# Sheet1.net
KiCad netlist of a schematic drawn in Altium Designer
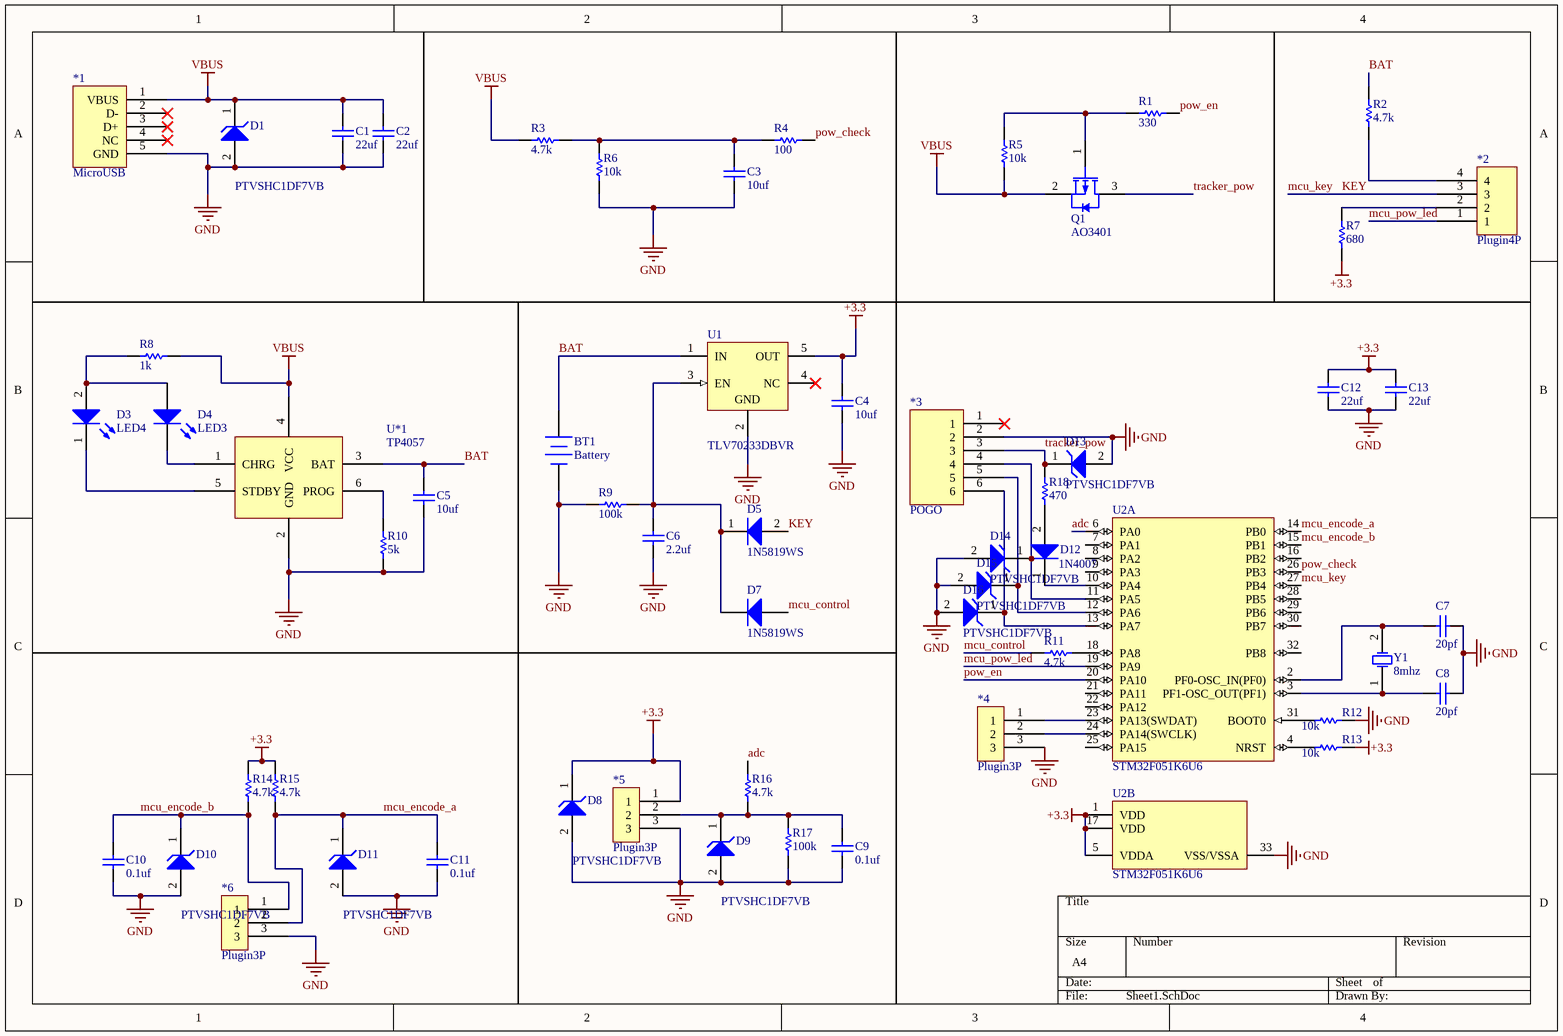
[diagram p0: Sheet1.SchDoc]

(export (version "E")
  (design (tool "Eeschema 10.0.6"))
  (components
    (comp (ref "*1") (value "MicroUSB") (footprint "MicroUSB") (libsource (lib "Schlib1") (part "MicroUSB")))
    (comp (ref "*2") (value "Plugin4P") (footprint "PLUGIN4P") (libsource (lib "Schlib1") (part "Plugin4P")))
    (comp (ref "*3") (value "POGO") (footprint "POGO") (libsource (lib "Schlib1") (part "POGO")))
    (comp (ref "*4") (value "Plugin3P") (footprint "Plugin3P") (libsource (lib "Schlib1") (part "Plugin3P")))
    (comp (ref "*5") (value "Plugin3P") (footprint "Plugin3P") (libsource (lib "Schlib1") (part "Plugin3P")))
    (comp (ref "*6") (value "Plugin3P") (footprint "Plugin3P") (libsource (lib "Schlib1") (part "Plugin3P")))
    (comp (ref "BT1")
      (value "Battery")
      (footprint "BAT-2")
      (description "Multicell Battery")
      (fields (field (name "PUBLISHER") "Altium Limited"))
      (libsource (lib "Miscellaneous Devices") (part "Battery"))
    )
    (comp (ref "C1")
      (value "22uf")
      (footprint "RESC2013X65X40LL15T20")
      (description "Capacitor")
      (fields (field (name "PUBLISHER") "Altium Limited"))
      (libsource (lib "Miscellaneous Devices") (part "Cap"))
    )
    (comp (ref "C2")
      (value "22uf")
      (footprint "RESC2013X65X40LL15T20")
      (description "Capacitor")
      (fields (field (name "PUBLISHER") "Altium Limited"))
      (libsource (lib "Miscellaneous Devices") (part "Cap"))
    )
    (comp (ref "C3")
      (value "10uf")
      (footprint "RESC2013X65X40LL15T20")
      (description "Capacitor")
      (fields (field (name "PUBLISHER") "Altium Limited"))
      (libsource (lib "Miscellaneous Devices") (part "Cap"))
    )
    (comp (ref "C4")
      (value "10uf")
      (footprint "RESC2013X65X40LL15T20")
      (description "Capacitor")
      (fields (field (name "PUBLISHER") "Altium Limited"))
      (libsource (lib "Miscellaneous Devices") (part "Cap"))
    )
    (comp (ref "C5")
      (value "10uf")
      (footprint "RESC2013X65X40LL15T20")
      (description "Capacitor")
      (fields (field (name "PUBLISHER") "Altium Limited"))
      (libsource (lib "Miscellaneous Devices") (part "Cap"))
    )
    (comp (ref "C6")
      (value "2.2uf")
      (footprint "RESC2013X65X40LL15T20")
      (description "Capacitor")
      (fields (field (name "PUBLISHER") "Altium Limited"))
      (libsource (lib "Miscellaneous Devices") (part "Cap"))
    )
    (comp (ref "C7")
      (value "20pf")
      (footprint "RESC2013X65X40LL15T20")
      (description "Capacitor")
      (fields (field (name "PUBLISHER") "Altium Limited"))
      (libsource (lib "Miscellaneous Devices") (part "Cap"))
    )
    (comp (ref "C8")
      (value "20pf")
      (footprint "RESC2013X65X40LL15T20")
      (description "Capacitor")
      (fields (field (name "PUBLISHER") "Altium Limited"))
      (libsource (lib "Miscellaneous Devices") (part "Cap"))
    )
    (comp (ref "C9")
      (value "0.1uf")
      (footprint "RESC2013X65X40LL15T20")
      (description "Capacitor")
      (fields (field (name "PUBLISHER") "Altium Limited"))
      (libsource (lib "Miscellaneous Devices") (part "Cap"))
    )
    (comp (ref "C10")
      (value "0.1uf")
      (footprint "RESC2013X65X40LL15T20")
      (description "Capacitor")
      (fields (field (name "PUBLISHER") "Altium Limited"))
      (libsource (lib "Miscellaneous Devices") (part "Cap"))
    )
    (comp (ref "C11")
      (value "0.1uf")
      (footprint "RESC2013X65X40LL15T20")
      (description "Capacitor")
      (fields (field (name "PUBLISHER") "Altium Limited"))
      (libsource (lib "Miscellaneous Devices") (part "Cap"))
    )
    (comp (ref "C12")
      (value "22uf")
      (footprint "RESC2013X65X40LL15T20")
      (description "Capacitor")
      (fields (field (name "PUBLISHER") "Altium Limited"))
      (libsource (lib "Miscellaneous Devices") (part "Cap"))
    )
    (comp (ref "C13")
      (value "22uf")
      (footprint "RESC2013X65X40LL15T20")
      (description "Capacitor")
      (fields (field (name "PUBLISHER") "Altium Limited"))
      (libsource (lib "Miscellaneous Devices") (part "Cap"))
    )
    (comp (ref "D1")
      (value "PTVSHC1DF7VB")
      (footprint "ONSC-SOD-123-2-425-04_V")
      (description "Zener Voltage Regulator, 500 mW, 2-Pin SOD-123, Pb-Free, Tape and Reel")
      (fields (field (name "MANUFACTURER") "On Semiconductor") (field (name "PARTNUMBER") "MMSZ39T1G"))
      (libsource (lib "ON Semi Zener Diodes") (part "MMSZ39T1G"))
    )
    (comp (ref "D3")
      (value "LED4")
      (footprint "RESC2013X65X40LL15T20")
      (description "Typical BLUE SiC LED")
      (fields (field (name "PUBLISHER") "Altium Limited"))
      (libsource (lib "") (part "LED3_1"))
    )
    (comp (ref "D4")
      (value "LED3")
      (footprint "RESC2013X65X40LL15T20")
      (description "Typical BLUE SiC LED")
      (fields (field (name "PUBLISHER") "Altium Limited"))
      (libsource (lib "Miscellaneous Devices") (part "LED3"))
    )
    (comp (ref "D5")
      (value "1N5819WS")
      (footprint "ONSC-SOD-323-2-477-02_V")
      (description "3 Amp General Purpose Rectifier")
      (fields (field (name "PUBLISHER") "Altium Limited"))
      (libsource (lib "Miscellaneous Devices") (part "Diode 1N5402"))
    )
    (comp (ref "D7")
      (value "1N5819WS")
      (footprint "ONSC-SOD-323-2-477-02_V")
      (description "3 Amp General Purpose Rectifier")
      (fields (field (name "PUBLISHER") "Altium Limited"))
      (libsource (lib "") (part "Diode 1N5402_1"))
    )
    (comp (ref "D8")
      (value "PTVSHC1DF7VB")
      (footprint "ONSC-SOD-123-2-425-04_V")
      (description "Zener Voltage Regulator, 500 mW, 2-Pin SOD-123, Pb-Free, Tape and Reel")
      (fields (field (name "MANUFACTURER") "On Semiconductor") (field (name "PARTNUMBER") "MMSZ39T1G"))
      (libsource (lib "ON Semi Zener Diodes") (part "MMSZ39T1G"))
    )
    (comp (ref "D9")
      (value "PTVSHC1DF7VB")
      (footprint "ONSC-SOD-123-2-425-04_V")
      (description "Zener Voltage Regulator, 500 mW, 2-Pin SOD-123, Pb-Free, Tape and Reel")
      (fields (field (name "MANUFACTURER") "On Semiconductor") (field (name "PARTNUMBER") "MMSZ39T1G"))
      (libsource (lib "ON Semi Zener Diodes") (part "MMSZ39T1G"))
    )
    (comp (ref "D10")
      (value "PTVSHC1DF7VB")
      (footprint "ONSC-SOD-123-2-425-04_V")
      (description "Zener Voltage Regulator, 500 mW, 2-Pin SOD-123, Pb-Free, Tape and Reel")
      (fields (field (name "MANUFACTURER") "On Semiconductor") (field (name "PARTNUMBER") "MMSZ39T1G"))
      (libsource (lib "ON Semi Zener Diodes") (part "MMSZ39T1G"))
    )
    (comp (ref "D11")
      (value "PTVSHC1DF7VB")
      (footprint "ONSC-SOD-123-2-425-04_V")
      (description "Zener Voltage Regulator, 500 mW, 2-Pin SOD-123, Pb-Free, Tape and Reel")
      (fields (field (name "MANUFACTURER") "On Semiconductor") (field (name "PARTNUMBER") "MMSZ39T1G"))
      (libsource (lib "ON Semi Zener Diodes") (part "MMSZ39T1G"))
    )
    (comp (ref "D12")
      (value "1N4007")
      (footprint "ONSC-SOD-323-2-477-02_V")
      (description "3 Amp General Purpose Rectifier")
      (fields (field (name "PUBLISHER") "Altium Limited"))
      (libsource (lib "Miscellaneous Devices") (part "Diode 1N5402"))
    )
    (comp (ref "D13")
      (value "PTVSHC1DF7VB")
      (footprint "ONSC-SOD-123-2-425-04_V")
      (description "Zener Voltage Regulator, 500 mW, 2-Pin SOD-123, Pb-Free, Tape and Reel")
      (fields (field (name "MANUFACTURER") "On Semiconductor") (field (name "PARTNUMBER") "MMSZ39T1G"))
      (libsource (lib "ON Semi Zener Diodes") (part "MMSZ39T1G"))
    )
    (comp (ref "D14")
      (value "PTVSHC1DF7VB")
      (footprint "ONSC-SOD-123-2-425-04_V")
      (description "Zener Voltage Regulator, 500 mW, 2-Pin SOD-123, Pb-Free, Tape and Reel")
      (fields (field (name "MANUFACTURER") "On Semiconductor") (field (name "PARTNUMBER") "MMSZ39T1G"))
      (libsource (lib "ON Semi Zener Diodes") (part "MMSZ39T1G"))
    )
    (comp (ref "D15")
      (value "PTVSHC1DF7VB")
      (footprint "ONSC-SOD-123-2-425-04_V")
      (description "Zener Voltage Regulator, 500 mW, 2-Pin SOD-123, Pb-Free, Tape and Reel")
      (fields (field (name "MANUFACTURER") "On Semiconductor") (field (name "PARTNUMBER") "MMSZ39T1G"))
      (libsource (lib "ON Semi Zener Diodes") (part "MMSZ39T1G"))
    )
    (comp (ref "D16")
      (value "PTVSHC1DF7VB")
      (footprint "ONSC-SOD-123-2-425-04_V")
      (description "Zener Voltage Regulator, 500 mW, 2-Pin SOD-123, Pb-Free, Tape and Reel")
      (fields (field (name "MANUFACTURER") "On Semiconductor") (field (name "PARTNUMBER") "MMSZ39T1G"))
      (libsource (lib "ON Semi Zener Diodes") (part "MMSZ39T1G"))
    )
    (comp (ref "Q1")
      (value "AO3401")
      (footprint "INF-PG-SOT23_N")
      (fields (field (name "MANUFACTURER") "Infineon") (field (name "PARTNUMBER") "BSS215P H6327"))
      (libsource (lib "Infineon_Power_MOSFET") (part "BSS215P H6327"))
    )
    (comp (ref "R1")
      (value "330")
      (footprint "RESC2013X65X40LL15T20")
      (description "Chip Resistor, 0 Ohm, 0.125 W, -55 to 125 degC, 0805 (2012 Metric), RoHS, Tape and Reel")
      (libsource (lib "TE Passive Components") (part "CRG0805ZR"))
    )
    (comp (ref "R2")
      (value "4.7k")
      (footprint "RESC2013X65X40LL15T20")
      (description "Chip Resistor, 0 Ohm, 0.125 W, -55 to 125 degC, 0805 (2012 Metric), RoHS, Tape and Reel")
      (libsource (lib "TE Passive Components") (part "CRG0805ZR"))
    )
    (comp (ref "R3")
      (value "4.7k")
      (footprint "RESC2013X65X40LL15T20")
      (description "Chip Resistor, 0 Ohm, 0.125 W, -55 to 125 degC, 0805 (2012 Metric), RoHS, Tape and Reel")
      (libsource (lib "TE Passive Components") (part "CRG0805ZR"))
    )
    (comp (ref "R4")
      (value "100")
      (footprint "RESC2013X65X40LL15T20")
      (description "Chip Resistor, 0 Ohm, 0.125 W, -55 to 125 degC, 0805 (2012 Metric), RoHS, Tape and Reel")
      (libsource (lib "TE Passive Components") (part "CRG0805ZR"))
    )
    (comp (ref "R5")
      (value "10k")
      (footprint "RESC2013X65X40LL15T20")
      (description "Chip Resistor, 0 Ohm, 0.125 W, -55 to 125 degC, 0805 (2012 Metric), RoHS, Tape and Reel")
      (libsource (lib "TE Passive Components") (part "CRG0805ZR"))
    )
    (comp (ref "R6")
      (value "10k")
      (footprint "RESC2013X65X40LL15T20")
      (description "Chip Resistor, 0 Ohm, 0.125 W, -55 to 125 degC, 0805 (2012 Metric), RoHS, Tape and Reel")
      (libsource (lib "TE Passive Components") (part "CRG0805ZR"))
    )
    (comp (ref "R7")
      (value "680")
      (footprint "RESC2013X65X40LL15T20")
      (description "Chip Resistor, 0 Ohm, 0.125 W, -55 to 125 degC, 0805 (2012 Metric), RoHS, Tape and Reel")
      (libsource (lib "TE Passive Components") (part "CRG0805ZR"))
    )
    (comp (ref "R8")
      (value "1k")
      (footprint "RESC2013X65X40LL15T20")
      (description "Chip Resistor, 0 Ohm, 0.125 W, -55 to 125 degC, 0805 (2012 Metric), RoHS, Tape and Reel")
      (libsource (lib "TE Passive Components") (part "CRG0805ZR"))
    )
    (comp (ref "R9")
      (value "100k")
      (footprint "RESC2013X65X40LL15T20")
      (description "Chip Resistor, 0 Ohm, 0.125 W, -55 to 125 degC, 0805 (2012 Metric), RoHS, Tape and Reel")
      (libsource (lib "TE Passive Components") (part "CRG0805ZR"))
    )
    (comp (ref "R10")
      (value "5k")
      (footprint "RESC2013X65X40LL15T20")
      (description "Chip Resistor, 0 Ohm, 0.125 W, -55 to 125 degC, 0805 (2012 Metric), RoHS, Tape and Reel")
      (libsource (lib "TE Passive Components") (part "CRG0805ZR"))
    )
    (comp (ref "R11")
      (value "4.7k")
      (footprint "RESC2013X65X40LL15T20")
      (description "Chip Resistor, 0 Ohm, 0.125 W, -55 to 125 degC, 0805 (2012 Metric), RoHS, Tape and Reel")
      (libsource (lib "TE Passive Components") (part "CRG0805ZR"))
    )
    (comp (ref "R12")
      (value "10k")
      (footprint "RESC2013X65X40LL15T20")
      (description "Chip Resistor, 0 Ohm, 0.125 W, -55 to 125 degC, 0805 (2012 Metric), RoHS, Tape and Reel")
      (libsource (lib "TE Passive Components") (part "CRG0805ZR"))
    )
    (comp (ref "R13")
      (value "10k")
      (footprint "RESC2013X65X40LL15T20")
      (description "Chip Resistor, 0 Ohm, 0.125 W, -55 to 125 degC, 0805 (2012 Metric), RoHS, Tape and Reel")
      (libsource (lib "TE Passive Components") (part "CRG0805ZR"))
    )
    (comp (ref "R14")
      (value "4.7k")
      (footprint "RESC2013X65X40LL15T20")
      (description "Chip Resistor, 0 Ohm, 0.125 W, -55 to 125 degC, 0805 (2012 Metric), RoHS, Tape and Reel")
      (libsource (lib "TE Passive Components") (part "CRG0805ZR"))
    )
    (comp (ref "R15")
      (value "4.7k")
      (footprint "RESC2013X65X40LL15T20")
      (description "Chip Resistor, 0 Ohm, 0.125 W, -55 to 125 degC, 0805 (2012 Metric), RoHS, Tape and Reel")
      (libsource (lib "TE Passive Components") (part "CRG0805ZR"))
    )
    (comp (ref "R16")
      (value "4.7k")
      (footprint "RESC2013X65X40LL15T20")
      (description "Chip Resistor, 0 Ohm, 0.125 W, -55 to 125 degC, 0805 (2012 Metric), RoHS, Tape and Reel")
      (libsource (lib "TE Passive Components") (part "CRG0805ZR"))
    )
    (comp (ref "R17")
      (value "100k")
      (footprint "RESC2013X65X40LL15T20")
      (description "Chip Resistor, 0 Ohm, 0.125 W, -55 to 125 degC, 0805 (2012 Metric), RoHS, Tape and Reel")
      (libsource (lib "TE Passive Components") (part "CRG0805ZR"))
    )
    (comp (ref "R18")
      (value "470")
      (footprint "RESC2013X65X40LL15T20")
      (description "Chip Resistor, 0 Ohm, 0.125 W, -55 to 125 degC, 0805 (2012 Metric), RoHS, Tape and Reel")
      (libsource (lib "TE Passive Components") (part "CRG0805ZR"))
    )
    (comp (ref "U*1") (value "TP4057") (footprint "TP4057") (libsource (lib "Schlib1") (part "TP4057")))
    (comp (ref "U1")
      (value "TLV70233DBVR")
      (footprint "TI-DBV5_N")
      (fields (field (name "MANUFACTURER") "Texas Instruments"))
      (libsource (lib "TI Power Management Linear Regulator Single Channel LDO (0-350mA)") (part "TLV70233DBVR"))
    )
    (comp (ref "U2")
      (value "STM32F051K6U6")
      (footprint "STM-UFQFPN32_N")
      (libsource (lib "STMicroelectronics STM32 F0") (part "STM32F051K6U6"))
    )
    (comp (ref "Y1")
      (value "8mhz")
      (footprint "XTAL")
      (description "Crystal Oscillator")
      (fields (field (name "PUBLISHER") "Altium Limited"))
      (libsource (lib "Miscellaneous Devices") (part "XTAL"))
    )
  )
  (nets
    (net (code "1") (name "+3.3") (class "Default")
      (node (ref "*5") (pin "1") (pinfunction "1_1") (pintype "passive"))
      (node (ref "C12") (pin "2") (pinfunction "2_2") (pintype "passive"))
      (node (ref "C13") (pin "2") (pinfunction "2_2") (pintype "passive"))
      (node (ref "C4") (pin "2") (pinfunction "2_2") (pintype "passive"))
      (node (ref "D8") (pin "1") (pinfunction "K_1") (pintype "passive"))
      (node (ref "R13") (pin "2") (pinfunction "2_2") (pintype "passive"))
      (node (ref "R14") (pin "2") (pinfunction "2_2") (pintype "passive"))
      (node (ref "R15") (pin "2") (pinfunction "2_2") (pintype "passive"))
      (node (ref "R7") (pin "2") (pinfunction "2_2") (pintype "passive"))
      (node (ref "U1") (pin "5") (pinfunction "OUT_5") (pintype "power_in"))
      (node (ref "U2") (pin "1") (pinfunction "VDD_1") (pintype "power_in"))
      (node (ref "U2") (pin "17") (pinfunction "VDD_17") (pintype "power_in"))
      (node (ref "U2") (pin "5") (pinfunction "VDDA_5") (pintype "power_in"))
    )
    (net (code "2") (name "/BAT") (class "Default")
      (node (ref "BT1") (pin "1") (pinfunction "+_1") (pintype "passive"))
      (node (ref "C5") (pin "2") (pinfunction "2_2") (pintype "passive"))
      (node (ref "R2") (pin "2") (pinfunction "2_2") (pintype "passive"))
      (node (ref "U*1") (pin "3") (pinfunction "BAT_3") (pintype "passive"))
      (node (ref "U1") (pin "1") (pinfunction "IN_1") (pintype "power_in"))
    )
    (net (code "3") (name "/KEY") (class "Default")
      (node (ref "*2") (pin "3") (pinfunction "3_3") (pintype "passive"))
      (node (ref "D5") (pin "2") (pinfunction "A_2") (pintype "passive"))
      (node (ref "U2") (pin "27") (pinfunction "PB4_27") (pintype "bidirectional"))
    )
    (net (code "4") (name "/adc") (class "Default")
      (node (ref "R16") (pin "2") (pinfunction "2_2") (pintype "passive"))
      (node (ref "U2") (pin "6") (pinfunction "PA0_6") (pintype "bidirectional"))
    )
    (net (code "5") (name "/mcu_control") (class "Default")
      (node (ref "D7") (pin "2") (pinfunction "A_2") (pintype "passive"))
      (node (ref "R11") (pin "1") (pinfunction "1_1") (pintype "passive"))
    )
    (net (code "6") (name "/mcu_encode_a") (class "Default")
      (node (ref "*6") (pin "2") (pinfunction "2_2") (pintype "passive"))
      (node (ref "C11") (pin "1") (pinfunction "1_1") (pintype "passive"))
      (node (ref "D11") (pin "1") (pinfunction "K_1") (pintype "passive"))
      (node (ref "R15") (pin "1") (pinfunction "1_1") (pintype "passive"))
      (node (ref "U2") (pin "14") (pinfunction "PB0_14") (pintype "bidirectional"))
    )
    (net (code "7") (name "/mcu_encode_b") (class "Default")
      (node (ref "*6") (pin "1") (pinfunction "1_1") (pintype "passive"))
      (node (ref "C10") (pin "1") (pinfunction "1_1") (pintype "passive"))
      (node (ref "D10") (pin "1") (pinfunction "K_1") (pintype "passive"))
      (node (ref "R14") (pin "1") (pinfunction "1_1") (pintype "passive"))
      (node (ref "U2") (pin "15") (pinfunction "PB1_15") (pintype "bidirectional"))
    )
    (net (code "8") (name "/mcu_pow_led") (class "Default")
      (node (ref "*2") (pin "1") (pinfunction "1_1") (pintype "passive"))
      (node (ref "U2") (pin "19") (pinfunction "PA9_19") (pintype "bidirectional"))
    )
    (net (code "9") (name "/pow_check") (class "Default")
      (node (ref "R4") (pin "2") (pinfunction "2_2") (pintype "passive"))
      (node (ref "U2") (pin "26") (pinfunction "PB3_26") (pintype "bidirectional"))
    )
    (net (code "10") (name "/pow_en") (class "Default")
      (node (ref "R1") (pin "2") (pinfunction "2_2") (pintype "passive"))
      (node (ref "U2") (pin "20") (pinfunction "PA10_20") (pintype "bidirectional"))
    )
    (net (code "11") (name "/tracker_pow") (class "Default")
      (node (ref "*3") (pin "3") (pinfunction "3_3") (pintype "passive"))
      (node (ref "D13") (pin "1") (pinfunction "K_1") (pintype "passive"))
      (node (ref "Q1") (pin "3") (pinfunction "DRAIN_3") (pintype "passive"))
      (node (ref "R18") (pin "2") (pinfunction "2_2") (pintype "passive"))
    )
    (net (code "12") (name "GND") (class "Default")
      (node (ref "*1") (pin "5") (pinfunction "GND_5") (pintype "passive"))
      (node (ref "*3") (pin "2") (pinfunction "2_2") (pintype "passive"))
      (node (ref "*4") (pin "3") (pinfunction "3_3") (pintype "passive"))
      (node (ref "*5") (pin "3") (pinfunction "3_3") (pintype "passive"))
      (node (ref "*6") (pin "3") (pinfunction "3_3") (pintype "passive"))
      (node (ref "BT1") (pin "2") (pinfunction "-_2") (pintype "passive"))
      (node (ref "C1") (pin "1") (pinfunction "1_1") (pintype "passive"))
      (node (ref "C10") (pin "2") (pinfunction "2_2") (pintype "passive"))
      (node (ref "C11") (pin "2") (pinfunction "2_2") (pintype "passive"))
      (node (ref "C12") (pin "1") (pinfunction "1_1") (pintype "passive"))
      (node (ref "C13") (pin "1") (pinfunction "1_1") (pintype "passive"))
      (node (ref "C2") (pin "1") (pinfunction "1_1") (pintype "passive"))
      (node (ref "C3") (pin "1") (pinfunction "1_1") (pintype "passive"))
      (node (ref "C4") (pin "1") (pinfunction "1_1") (pintype "passive"))
      (node (ref "C5") (pin "1") (pinfunction "1_1") (pintype "passive"))
      (node (ref "C6") (pin "1") (pinfunction "1_1") (pintype "passive"))
      (node (ref "C7") (pin "1") (pinfunction "1_1") (pintype "passive"))
      (node (ref "C8") (pin "1") (pinfunction "1_1") (pintype "passive"))
      (node (ref "C9") (pin "2") (pinfunction "2_2") (pintype "passive"))
      (node (ref "D1") (pin "2") (pinfunction "A_2") (pintype "passive"))
      (node (ref "D10") (pin "2") (pinfunction "A_2") (pintype "passive"))
      (node (ref "D11") (pin "2") (pinfunction "A_2") (pintype "passive"))
      (node (ref "D13") (pin "2") (pinfunction "A_2") (pintype "passive"))
      (node (ref "D14") (pin "2") (pinfunction "A_2") (pintype "passive"))
      (node (ref "D15") (pin "2") (pinfunction "A_2") (pintype "passive"))
      (node (ref "D16") (pin "2") (pinfunction "A_2") (pintype "passive"))
      (node (ref "D8") (pin "2") (pinfunction "A_2") (pintype "passive"))
      (node (ref "D9") (pin "2") (pinfunction "A_2") (pintype "passive"))
      (node (ref "R10") (pin "1") (pinfunction "1_1") (pintype "passive"))
      (node (ref "R12") (pin "2") (pinfunction "2_2") (pintype "passive"))
      (node (ref "R17") (pin "1") (pinfunction "1_1") (pintype "passive"))
      (node (ref "R6") (pin "1") (pinfunction "1_1") (pintype "passive"))
      (node (ref "R9") (pin "2") (pinfunction "2_2") (pintype "passive"))
      (node (ref "U*1") (pin "2") (pinfunction "GND_2") (pintype "power_in"))
      (node (ref "U1") (pin "2") (pinfunction "GND_2") (pintype "power_in"))
      (node (ref "U2") (pin "33") (pinfunction "VSS/VSSA_33") (pintype "power_in"))
    )
    (net (code "13") (name "Net-(*2-Pad2)") (class "Default")
      (node (ref "*2") (pin "2") (pinfunction "2_2") (pintype "passive"))
      (node (ref "R7") (pin "1") (pinfunction "1_1") (pintype "passive"))
    )
    (net (code "14") (name "Net-(*2-Pad4)") (class "Default")
      (node (ref "*2") (pin "4") (pinfunction "4_4") (pintype "passive"))
      (node (ref "R2") (pin "1") (pinfunction "1_1") (pintype "passive"))
    )
    (net (code "15") (name "Net-(C3-Pad2)") (class "Default")
      (node (ref "C3") (pin "2") (pinfunction "2_2") (pintype "passive"))
      (node (ref "R3") (pin "2") (pinfunction "2_2") (pintype "passive"))
      (node (ref "R4") (pin "1") (pinfunction "1_1") (pintype "passive"))
      (node (ref "R6") (pin "2") (pinfunction "2_2") (pintype "passive"))
    )
    (net (code "16") (name "Net-(D3-A)") (class "Default")
      (node (ref "D3") (pin "2") (pinfunction "A_2") (pintype "passive"))
      (node (ref "D4") (pin "2") (pinfunction "A_2") (pintype "passive"))
      (node (ref "R8") (pin "1") (pinfunction "1_1") (pintype "passive"))
    )
    (net (code "17") (name "Net-(D3-K)") (class "Default")
      (node (ref "D3") (pin "1") (pinfunction "K_1") (pintype "passive"))
      (node (ref "U*1") (pin "5") (pinfunction "STDBY_5") (pintype "passive"))
    )
    (net (code "18") (name "Net-(D4-K)") (class "Default")
      (node (ref "D4") (pin "1") (pinfunction "K_1") (pintype "passive"))
      (node (ref "U*1") (pin "1") (pinfunction "CHRG_1") (pintype "passive"))
    )
    (net (code "19") (name "Net-(D5-K)") (class "Default")
      (node (ref "C6") (pin "2") (pinfunction "2_2") (pintype "passive"))
      (node (ref "D5") (pin "1") (pinfunction "K_1") (pintype "passive"))
      (node (ref "D7") (pin "1") (pinfunction "K_1") (pintype "passive"))
      (node (ref "R9") (pin "1") (pinfunction "1_1") (pintype "passive"))
      (node (ref "U1") (pin "3") (pinfunction "EN_3") (pintype "input"))
    )
    (net (code "20") (name "Net-(D9-K)") (class "Default")
      (node (ref "*5") (pin "2") (pinfunction "2_2") (pintype "passive"))
      (node (ref "C9") (pin "1") (pinfunction "1_1") (pintype "passive"))
      (node (ref "D9") (pin "1") (pinfunction "K_1") (pintype "passive"))
      (node (ref "R16") (pin "1") (pinfunction "1_1") (pintype "passive"))
      (node (ref "R17") (pin "2") (pinfunction "2_2") (pintype "passive"))
    )
    (net (code "21") (name "Net-(D12-A)") (class "Default")
      (node (ref "D12") (pin "2") (pinfunction "A_2") (pintype "passive"))
      (node (ref "R18") (pin "1") (pinfunction "1_1") (pintype "passive"))
    )
    (net (code "22") (name "Net-(D12-K)") (class "Default")
      (node (ref "D12") (pin "1") (pinfunction "K_1") (pintype "passive"))
      (node (ref "U2") (pin "10") (pinfunction "PA4_10") (pintype "bidirectional"))
    )
    (net (code "23") (name "Net-(D14-K)") (class "Default")
      (node (ref "*3") (pin "4") (pinfunction "4_4") (pintype "passive"))
      (node (ref "D14") (pin "1") (pinfunction "K_1") (pintype "passive"))
      (node (ref "U2") (pin "11") (pinfunction "PA5_11") (pintype "bidirectional"))
    )
    (net (code "24") (name "Net-(D15-K)") (class "Default")
      (node (ref "*3") (pin "5") (pinfunction "5_5") (pintype "passive"))
      (node (ref "D15") (pin "1") (pinfunction "K_1") (pintype "passive"))
      (node (ref "U2") (pin "12") (pinfunction "PA6_12") (pintype "bidirectional"))
    )
    (net (code "25") (name "Net-(D16-K)") (class "Default")
      (node (ref "*3") (pin "6") (pinfunction "6_6") (pintype "passive"))
      (node (ref "D16") (pin "1") (pinfunction "K_1") (pintype "passive"))
      (node (ref "U2") (pin "13") (pinfunction "PA7_13") (pintype "bidirectional"))
    )
    (net (code "26") (name "Net-(Q1-GATE)") (class "Default")
      (node (ref "Q1") (pin "1") (pinfunction "GATE_1") (pintype "passive"))
      (node (ref "R1") (pin "1") (pinfunction "1_1") (pintype "passive"))
      (node (ref "R5") (pin "2") (pinfunction "2_2") (pintype "passive"))
    )
    (net (code "27") (name "Net-(U*1-PROG)") (class "Default")
      (node (ref "R10") (pin "2") (pinfunction "2_2") (pintype "passive"))
      (node (ref "U*1") (pin "6") (pinfunction "PROG_6") (pintype "passive"))
    )
    (net (code "28") (name "Net-(U2A-BOOT0)") (class "Default")
      (node (ref "R12") (pin "1") (pinfunction "1_1") (pintype "passive"))
      (node (ref "U2") (pin "31") (pinfunction "BOOT0_31") (pintype "input"))
    )
    (net (code "29") (name "Net-(U2A-NRST)") (class "Default")
      (node (ref "R13") (pin "1") (pinfunction "1_1") (pintype "passive"))
      (node (ref "U2") (pin "4") (pinfunction "NRST_4") (pintype "bidirectional"))
    )
    (net (code "30") (name "Net-(U2A-PA8)") (class "Default")
      (node (ref "R11") (pin "2") (pinfunction "2_2") (pintype "passive"))
      (node (ref "U2") (pin "18") (pinfunction "PA8_18") (pintype "bidirectional"))
    )
    (net (code "31") (name "Net-(U2A-PA13(SWDAT))") (class "Default")
      (node (ref "*4") (pin "1") (pinfunction "1_1") (pintype "passive"))
      (node (ref "U2") (pin "23") (pinfunction "PA13(SWDAT)_23") (pintype "bidirectional"))
    )
    (net (code "32") (name "Net-(U2A-PA14(SWCLK))") (class "Default")
      (node (ref "*4") (pin "2") (pinfunction "2_2") (pintype "passive"))
      (node (ref "U2") (pin "24") (pinfunction "PA14(SWCLK)_24") (pintype "bidirectional"))
    )
    (net (code "33") (name "Net-(U2A-PF0-OSC_IN(PF0))") (class "Default")
      (node (ref "C7") (pin "2") (pinfunction "2_2") (pintype "passive"))
      (node (ref "U2") (pin "2") (pinfunction "PF0-OSC_IN(PF0)_2") (pintype "bidirectional"))
      (node (ref "Y1") (pin "2") (pinfunction "OSC2_2") (pintype "passive"))
    )
    (net (code "34") (name "Net-(U2A-PF1-OSC_OUT(PF1))") (class "Default")
      (node (ref "C8") (pin "2") (pinfunction "2_2") (pintype "passive"))
      (node (ref "U2") (pin "3") (pinfunction "PF1-OSC_OUT(PF1)_3") (pintype "bidirectional"))
      (node (ref "Y1") (pin "1") (pinfunction "OSC1_1") (pintype "passive"))
    )
    (net (code "35") (name "VBUS") (class "Default")
      (node (ref "*1") (pin "1") (pinfunction "VBUS_1") (pintype "passive"))
      (node (ref "C1") (pin "2") (pinfunction "2_2") (pintype "passive"))
      (node (ref "C2") (pin "2") (pinfunction "2_2") (pintype "passive"))
      (node (ref "D1") (pin "1") (pinfunction "K_1") (pintype "passive"))
      (node (ref "Q1") (pin "2") (pinfunction "SOURCE_2") (pintype "passive"))
      (node (ref "R3") (pin "1") (pinfunction "1_1") (pintype "passive"))
      (node (ref "R5") (pin "1") (pinfunction "1_1") (pintype "passive"))
      (node (ref "R8") (pin "2") (pinfunction "2_2") (pintype "passive"))
      (node (ref "U*1") (pin "4") (pinfunction "VCC_4") (pintype "power_in"))
    )
    (net (code "36") (name "unconnected-(*1-D+-Pad3)") (class "Default")
      (node (ref "*1") (pin "3") (pinfunction "D+_3") (pintype "passive+no_connect"))
    )
    (net (code "37") (name "unconnected-(*1-D--Pad2)") (class "Default")
      (node (ref "*1") (pin "2") (pinfunction "D-_2") (pintype "passive+no_connect"))
    )
    (net (code "38") (name "unconnected-(*1-NC-Pad4)") (class "Default")
      (node (ref "*1") (pin "4") (pinfunction "NC_4") (pintype "passive+no_connect"))
    )
    (net (code "39") (name "unconnected-(*3-Pad1)") (class "Default")
      (node (ref "*3") (pin "1") (pinfunction "1_1") (pintype "passive+no_connect"))
    )
    (net (code "40") (name "unconnected-(U1-NC-Pad4)") (class "Default")
      (node (ref "U1") (pin "4") (pinfunction "NC_4") (pintype "passive+no_connect"))
    )
    (net (code "41") (name "unconnected-(U2A-PA1-Pad7)") (class "Default")
      (node (ref "U2") (pin "7") (pinfunction "PA1_7") (pintype "bidirectional"))
    )
    (net (code "42") (name "unconnected-(U2A-PA2-Pad8)") (class "Default")
      (node (ref "U2") (pin "8") (pinfunction "PA2_8") (pintype "bidirectional"))
    )
    (net (code "43") (name "unconnected-(U2A-PA3-Pad9)") (class "Default")
      (node (ref "U2") (pin "9") (pinfunction "PA3_9") (pintype "bidirectional"))
    )
    (net (code "44") (name "unconnected-(U2A-PA11-Pad21)") (class "Default")
      (node (ref "U2") (pin "21") (pinfunction "PA11_21") (pintype "bidirectional"))
    )
    (net (code "45") (name "unconnected-(U2A-PA12-Pad22)") (class "Default")
      (node (ref "U2") (pin "22") (pinfunction "PA12_22") (pintype "bidirectional"))
    )
    (net (code "46") (name "unconnected-(U2A-PA15-Pad25)") (class "Default")
      (node (ref "U2") (pin "25") (pinfunction "PA15_25") (pintype "bidirectional"))
    )
    (net (code "47") (name "unconnected-(U2A-PB2-Pad16)") (class "Default")
      (node (ref "U2") (pin "16") (pinfunction "PB2_16") (pintype "bidirectional"))
    )
    (net (code "48") (name "unconnected-(U2A-PB5-Pad28)") (class "Default")
      (node (ref "U2") (pin "28") (pinfunction "PB5_28") (pintype "bidirectional"))
    )
    (net (code "49") (name "unconnected-(U2A-PB6-Pad29)") (class "Default")
      (node (ref "U2") (pin "29") (pinfunction "PB6_29") (pintype "bidirectional"))
    )
    (net (code "50") (name "unconnected-(U2A-PB7-Pad30)") (class "Default")
      (node (ref "U2") (pin "30") (pinfunction "PB7_30") (pintype "bidirectional"))
    )
    (net (code "51") (name "unconnected-(U2A-PB8-Pad32)") (class "Default")
      (node (ref "U2") (pin "32") (pinfunction "PB8_32") (pintype "bidirectional"))
    )
  )
)
